# Sch.net
KiCad netlist of a schematic drawn in Altium Designer
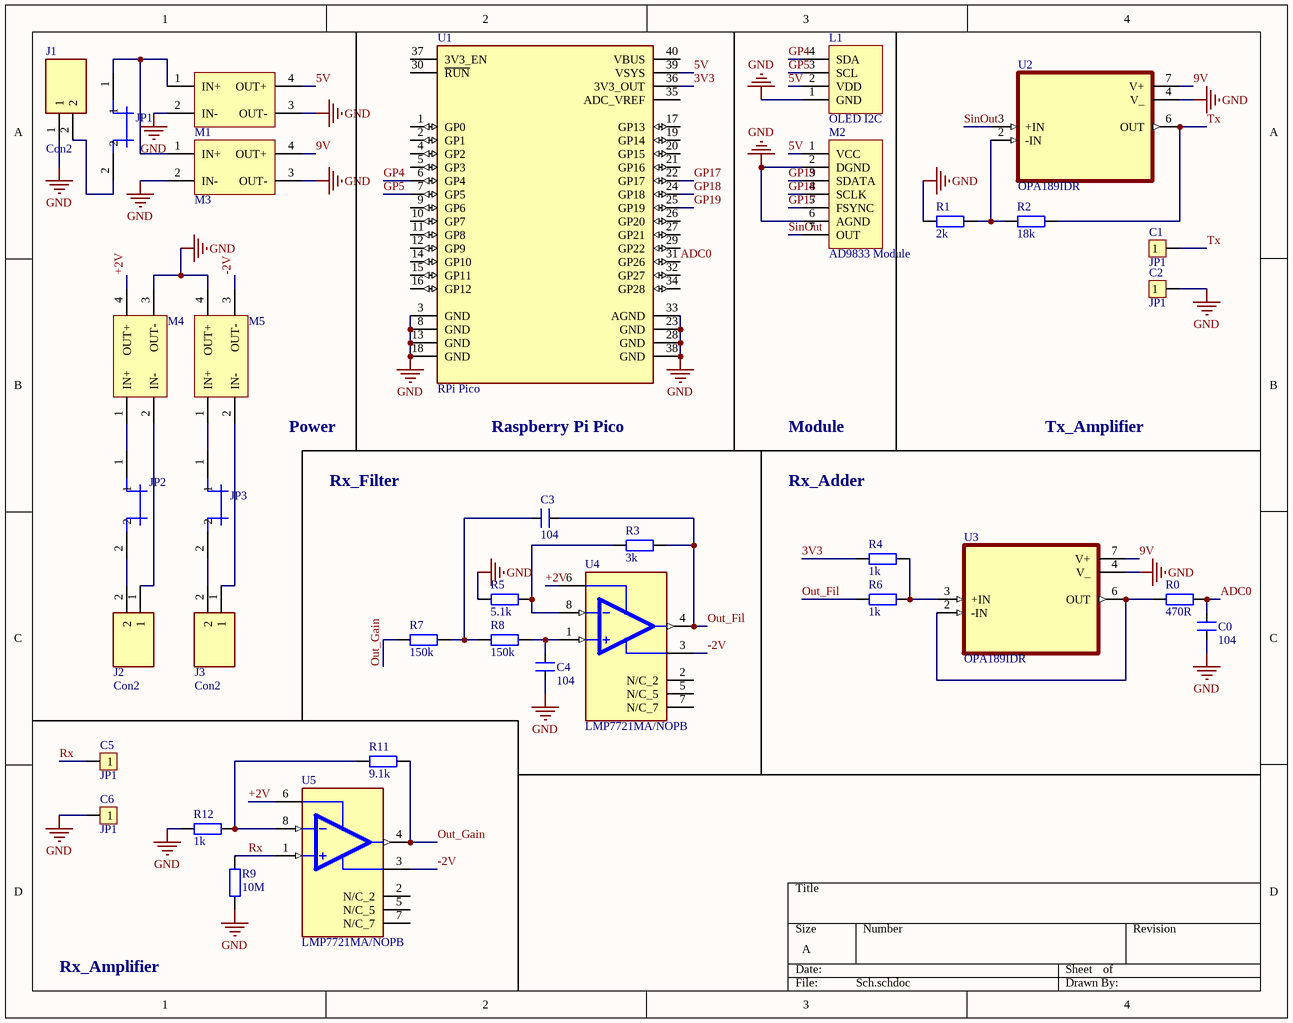
[diagram p0: Sch.schdoc]

(export (version "E")
  (design (tool "Eeschema 10.0.6"))
  (components
    (comp (ref "C0")
      (value "104")
      (footprint "CN2")
      (description "Cap np 104 => 105pF")
      (libsource (lib "Linhkien69") (part "CN2"))
    )
    (comp (ref "C1")
      (value "JP1")
      (footprint "JP1-D1T")
      (description "WR-PHD 2.54 mm Angled Socket Header")
      (fields
        (field (name "MANUFACTURER") "Würth Elektronik eiSos GmbH")
        (field (name "PARTNO") "613002143121")
        (field (name "CREATED BY") "Karrer Zheng")
      )
      (libsource (lib "") (part "JP1_1"))
    )
    (comp (ref "C2")
      (value "JP1")
      (footprint "JP1-D1T")
      (description "WR-PHD 2.54 mm Angled Socket Header")
      (fields
        (field (name "MANUFACTURER") "Würth Elektronik eiSos GmbH")
        (field (name "PARTNO") "613002143121")
        (field (name "CREATED BY") "Karrer Zheng")
      )
      (libsource (lib "") (part "JP1_1"))
    )
    (comp (ref "C3")
      (value "104")
      (footprint "CN2")
      (description "Cap np 104 => 105pF")
      (libsource (lib "Linhkien69") (part "CN2"))
    )
    (comp (ref "C4")
      (value "104")
      (footprint "CN2")
      (description "Cap np 104 => 105pF")
      (libsource (lib "Linhkien69") (part "CN2"))
    )
    (comp (ref "C5")
      (value "JP1")
      (footprint "JP1-D1T")
      (description "WR-PHD 2.54 mm Angled Socket Header")
      (fields
        (field (name "MANUFACTURER") "Würth Elektronik eiSos GmbH")
        (field (name "PARTNO") "613002143121")
        (field (name "CREATED BY") "Karrer Zheng")
      )
      (libsource (lib "Thư Viện Altium FULL HD") (part "JP1"))
    )
    (comp (ref "C6")
      (value "JP1")
      (footprint "JP1-D1T")
      (description "WR-PHD 2.54 mm Angled Socket Header")
      (fields
        (field (name "MANUFACTURER") "Würth Elektronik eiSos GmbH")
        (field (name "PARTNO") "613002143121")
        (field (name "CREATED BY") "Karrer Zheng")
      )
      (libsource (lib "Thư Viện Altium FULL HD") (part "JP1"))
    )
    (comp (ref "J1")
      (value "Con2")
      (footprint "Con_2")
      (fields (field (name "MP") "4-1123723-2"))
      (libsource (lib "") (part "Con2_1"))
    )
    (comp (ref "J2")
      (value "Con2")
      (footprint "Con_2")
      (fields (field (name "MP") "4-1123723-2"))
      (libsource (lib "Duy") (part "Con2"))
    )
    (comp (ref "J3")
      (value "Con2")
      (footprint "Con_2")
      (fields (field (name "MP") "4-1123723-2"))
      (libsource (lib "Duy") (part "Con2"))
    )
    (comp (ref "JP1")
      (value "Jump Con")
      (footprint "Jump_con")
      (description "Low Profile Jumper , Single Row, 2 Positions, 2.54mm (0.100in) Pitch")
      (fields (field (name "MF") "FCI") (field (name "MP") "68786-202LF"))
      (libsource (lib "Duy") (part "Jump Con"))
    )
    (comp (ref "JP2")
      (value "Jump Con")
      (footprint "Jump_con")
      (description "Low Profile Jumper , Single Row, 2 Positions, 2.54mm (0.100in) Pitch")
      (fields (field (name "MF") "FCI") (field (name "MP") "68786-202LF"))
      (libsource (lib "Duy") (part "Jump Con"))
    )
    (comp (ref "JP3")
      (value "Jump Con")
      (footprint "Jump_con")
      (description "Low Profile Jumper , Single Row, 2 Positions, 2.54mm (0.100in) Pitch")
      (fields (field (name "MF") "FCI") (field (name "MP") "68786-202LF"))
      (libsource (lib "Duy") (part "Jump Con"))
    )
    (comp (ref "L1") (value "OLED I2C") (footprint "OLED_I2C") (libsource (lib "Duy") (part "OLED I2C")))
    (comp (ref "M1")
      (value "XL6009 Module")
      (footprint "XL6009_Module")
      (libsource (lib "Duy") (part "XL6009 Module"))
    )
    (comp (ref "M2")
      (value "AD9833 Module")
      (footprint "AD9833_Module")
      (libsource (lib "Duy") (part "AD9833 Module"))
    )
    (comp (ref "M3")
      (value "XL6009 Module")
      (footprint "XL6009_Module")
      (libsource (lib "Duy") (part "XL6009 Module"))
    )
    (comp (ref "M4")
      (value "LM2596S Module")
      (footprint "LM2596S_Module")
      (libsource (lib "Duy") (part "LM2596S Module"))
    )
    (comp (ref "M5")
      (value "LM2596S Module")
      (footprint "LM2596S_Module")
      (libsource (lib "Duy") (part "LM2596S Module"))
    )
    (comp (ref "R0")
      (value "470R")
      (footprint "R1/4W")
      (description "Resistor 1/4W")
      (libsource (lib "syhaunguyen") (part "R1/4W"))
    )
    (comp (ref "R1")
      (value "2k")
      (footprint "R1/4W")
      (description "Resistor 1/4W")
      (libsource (lib "syhaunguyen") (part "R1/4W"))
    )
    (comp (ref "R2")
      (value "18k")
      (footprint "R1/4W")
      (description "Resistor 1/4W")
      (libsource (lib "syhaunguyen") (part "R1/4W"))
    )
    (comp (ref "R3")
      (value "3k")
      (footprint "R1/4W")
      (description "Resistor 1/4W")
      (libsource (lib "syhaunguyen") (part "R1/4W"))
    )
    (comp (ref "R4")
      (value "1k")
      (footprint "R1/4W")
      (description "Resistor 1/4W")
      (libsource (lib "syhaunguyen") (part "R1/4W"))
    )
    (comp (ref "R5")
      (value "5.1k")
      (footprint "R1/4W")
      (description "Resistor 1/4W")
      (libsource (lib "syhaunguyen") (part "R1/4W"))
    )
    (comp (ref "R6")
      (value "1k")
      (footprint "R1/4W")
      (description "Resistor 1/4W")
      (libsource (lib "syhaunguyen") (part "R1/4W"))
    )
    (comp (ref "R7")
      (value "150k")
      (footprint "R1/4W")
      (description "Resistor 1/4W")
      (libsource (lib "syhaunguyen") (part "R1/4W"))
    )
    (comp (ref "R8")
      (value "150k")
      (footprint "R1/4W")
      (description "Resistor 1/4W")
      (libsource (lib "syhaunguyen") (part "R1/4W"))
    )
    (comp (ref "R9")
      (value "10M")
      (footprint "R1/4W")
      (description "Resistor 1/4W")
      (libsource (lib "syhaunguyen") (part "R1/4W"))
    )
    (comp (ref "R11")
      (value "9.1k")
      (footprint "R1/4W")
      (description "Resistor 1/4W")
      (libsource (lib "syhaunguyen") (part "R1/4W"))
    )
    (comp (ref "R12")
      (value "1k")
      (footprint "R1/4W")
      (description "Resistor 1/4W")
      (libsource (lib "syhaunguyen") (part "R1/4W"))
    )
    (comp (ref "U1")
      (value "RPi Pico")
      (footprint "RPI_PICO")
      (description "RP2040 Raspberry Pi Pico - ARM Cortex-M0+ MCU 32-Bit Embedded Evaluation Board")
      (fields (field (name "MP") "SC0915"))
      (libsource (lib "Duy") (part "RPi Pico"))
    )
    (comp (ref "U2")
      (value "OPA189IDR")
      (footprint "SOIC127P599X175-8N")
      (fields (field (name "DIGI-KEY_PART_NUMBER") "296-48941-1-ND") (field (name "MF") "Texas Instruments"))
      (libsource (lib "Duy") (part "OPA189IDR"))
    )
    (comp (ref "U3")
      (value "OPA189IDR")
      (footprint "SOIC127P599X175-8N")
      (fields (field (name "DIGI-KEY_PART_NUMBER") "296-48941-1-ND") (field (name "MF") "Texas Instruments"))
      (libsource (lib "Duy") (part "OPA189IDR"))
    )
    (comp (ref "U4")
      (value "LMP7721MA/NOPB")
      (footprint "SOIC127P599X175-8N - duplicate")
      (description "3 Femtoampere Input Bias Current Precision Amplifier 8-SOIC -40 to 125")
      (fields (field (name "MF") "Texas Instruments"))
      (libsource (lib "Duy") (part "LMP7721MA/NOPB"))
    )
    (comp (ref "U5")
      (value "LMP7721MA/NOPB")
      (footprint "SOIC127P599X175-8N - duplicate")
      (description "3 Femtoampere Input Bias Current Precision Amplifier 8-SOIC -40 to 125")
      (fields (field (name "MF") "Texas Instruments"))
      (libsource (lib "Duy") (part "LMP7721MA/NOPB"))
    )
  )
  (nets
    (net (code "1") (name "/+2V") (class "Default")
      (node (ref "M4") (pin "4") (pinfunction "OUT+_4") (pintype "passive"))
      (node (ref "U4") (pin "6") (pinfunction "V+_6") (pintype "power_in"))
      (node (ref "U5") (pin "6") (pinfunction "V+_6") (pintype "power_in"))
    )
    (net (code "2") (name "/-2V") (class "Default")
      (node (ref "M5") (pin "3") (pinfunction "OUT-_3") (pintype "passive"))
      (node (ref "U4") (pin "3") (pinfunction "V-_3") (pintype "power_in"))
      (node (ref "U5") (pin "3") (pinfunction "V-_3") (pintype "power_in"))
    )
    (net (code "3") (name "/3V3") (class "Default")
      (node (ref "R4") (pin "1") (pinfunction "1_1") (pintype "passive"))
      (node (ref "U1") (pin "36") (pinfunction "3V3_OUT_36") (pintype "power_in"))
    )
    (net (code "4") (name "/5V") (class "Default")
      (node (ref "L1") (pin "2") (pinfunction "VDD_2") (pintype "passive"))
      (node (ref "M1") (pin "4") (pinfunction "OUT+_4") (pintype "passive"))
      (node (ref "M2") (pin "1") (pinfunction "VCC_1") (pintype "passive"))
      (node (ref "U1") (pin "39") (pinfunction "VSYS_39") (pintype "power_in"))
    )
    (net (code "5") (name "/9V") (class "Default")
      (node (ref "M3") (pin "4") (pinfunction "OUT+_4") (pintype "passive"))
      (node (ref "U2") (pin "7") (pinfunction "V+_7") (pintype "power_in"))
      (node (ref "U3") (pin "7") (pinfunction "V+_7") (pintype "power_in"))
    )
    (net (code "6") (name "/ADC0") (class "Default")
      (node (ref "C0") (pin "2") (pinfunction "2_2") (pintype "passive"))
      (node (ref "R0") (pin "2") (pinfunction "2_2") (pintype "passive"))
      (node (ref "U1") (pin "31") (pinfunction "GP26_31") (pintype "bidirectional"))
    )
    (net (code "7") (name "/GP4") (class "Default")
      (node (ref "L1") (pin "4") (pinfunction "SDA_4") (pintype "passive"))
      (node (ref "U1") (pin "6") (pinfunction "GP4_6") (pintype "bidirectional"))
    )
    (net (code "8") (name "/GP5") (class "Default")
      (node (ref "L1") (pin "3") (pinfunction "SCL_3") (pintype "passive"))
      (node (ref "U1") (pin "7") (pinfunction "GP5_7") (pintype "bidirectional"))
    )
    (net (code "9") (name "/GP17") (class "Default")
      (node (ref "M2") (pin "5") (pinfunction "FSYNC_5") (pintype "passive"))
      (node (ref "U1") (pin "22") (pinfunction "GP17_22") (pintype "bidirectional"))
    )
    (net (code "10") (name "/GP18") (class "Default")
      (node (ref "M2") (pin "4") (pinfunction "SCLK_4") (pintype "passive"))
      (node (ref "U1") (pin "24") (pinfunction "GP18_24") (pintype "bidirectional"))
    )
    (net (code "11") (name "/GP19") (class "Default")
      (node (ref "M2") (pin "3") (pinfunction "SDATA_3") (pintype "passive"))
      (node (ref "U1") (pin "25") (pinfunction "GP19_25") (pintype "bidirectional"))
    )
    (net (code "12") (name "/Out_Fil") (class "Default")
      (node (ref "C3") (pin "2") (pinfunction "2_2") (pintype "passive"))
      (node (ref "R3") (pin "2") (pinfunction "2_2") (pintype "passive"))
      (node (ref "R6") (pin "1") (pinfunction "1_1") (pintype "passive"))
      (node (ref "U4") (pin "4") (pinfunction "VOUT_4") (pintype "output"))
    )
    (net (code "13") (name "/Out_Gain") (class "Default")
      (node (ref "R11") (pin "2") (pinfunction "2_2") (pintype "passive"))
      (node (ref "R7") (pin "1") (pinfunction "1_1") (pintype "passive"))
      (node (ref "U5") (pin "4") (pinfunction "VOUT_4") (pintype "output"))
    )
    (net (code "14") (name "/Rx") (class "Default")
      (node (ref "C5") (pin "1") (pinfunction "1_1") (pintype "passive"))
      (node (ref "R9") (pin "1") (pinfunction "1_1") (pintype "passive"))
      (node (ref "U5") (pin "1") (pinfunction "IN+_1") (pintype "input"))
    )
    (net (code "15") (name "/SinOut") (class "Default")
      (node (ref "M2") (pin "7") (pinfunction "OUT_7") (pintype "passive"))
      (node (ref "U2") (pin "3") (pinfunction "+IN_3") (pintype "input"))
    )
    (net (code "16") (name "/Tx") (class "Default")
      (node (ref "C1") (pin "1") (pinfunction "1_1") (pintype "passive"))
      (node (ref "R2") (pin "2") (pinfunction "2_2") (pintype "passive"))
      (node (ref "U2") (pin "6") (pinfunction "OUT_6") (pintype "output"))
    )
    (net (code "17") (name "GND") (class "Default")
      (node (ref "C0") (pin "1") (pinfunction "1_1") (pintype "passive"))
      (node (ref "C2") (pin "1") (pinfunction "1_1") (pintype "passive"))
      (node (ref "C4") (pin "1") (pinfunction "1_1") (pintype "passive"))
      (node (ref "C6") (pin "1") (pinfunction "1_1") (pintype "passive"))
      (node (ref "J1") (pin "1") (pinfunction "1_1") (pintype "passive"))
      (node (ref "L1") (pin "1") (pinfunction "GND_1") (pintype "passive"))
      (node (ref "M1") (pin "2") (pinfunction "IN-_2") (pintype "passive"))
      (node (ref "M1") (pin "3") (pinfunction "OUT-_3") (pintype "passive"))
      (node (ref "M2") (pin "2") (pinfunction "DGND_2") (pintype "passive"))
      (node (ref "M2") (pin "6") (pinfunction "AGND_6") (pintype "passive"))
      (node (ref "M3") (pin "2") (pinfunction "IN-_2") (pintype "passive"))
      (node (ref "M3") (pin "3") (pinfunction "OUT-_3") (pintype "passive"))
      (node (ref "M4") (pin "3") (pinfunction "OUT-_3") (pintype "passive"))
      (node (ref "M5") (pin "4") (pinfunction "OUT+_4") (pintype "passive"))
      (node (ref "R1") (pin "1") (pinfunction "1_1") (pintype "passive"))
      (node (ref "R12") (pin "2") (pinfunction "2_2") (pintype "passive"))
      (node (ref "R5") (pin "1") (pinfunction "1_1") (pintype "passive"))
      (node (ref "R9") (pin "2") (pinfunction "2_2") (pintype "passive"))
      (node (ref "U1") (pin "13") (pinfunction "GND_13") (pintype "power_in"))
      (node (ref "U1") (pin "18") (pinfunction "GND_18") (pintype "power_in"))
      (node (ref "U1") (pin "23") (pinfunction "GND_23") (pintype "power_in"))
      (node (ref "U1") (pin "28") (pinfunction "GND_28") (pintype "power_in"))
      (node (ref "U1") (pin "3") (pinfunction "GND_3") (pintype "power_in"))
      (node (ref "U1") (pin "33") (pinfunction "AGND_33") (pintype "power_in"))
      (node (ref "U1") (pin "38") (pinfunction "GND_38") (pintype "power_in"))
      (node (ref "U1") (pin "8") (pinfunction "GND_8") (pintype "power_in"))
      (node (ref "U2") (pin "4") (pinfunction "V__4") (pintype "power_in"))
      (node (ref "U3") (pin "4") (pinfunction "V__4") (pintype "power_in"))
    )
    (net (code "18") (name "Net-(C3-Pad1)") (class "Default")
      (node (ref "C3") (pin "1") (pinfunction "1_1") (pintype "passive"))
      (node (ref "R7") (pin "2") (pinfunction "2_2") (pintype "passive"))
      (node (ref "R8") (pin "1") (pinfunction "1_1") (pintype "passive"))
    )
    (net (code "19") (name "Net-(J1-Pad2)") (class "Default")
      (node (ref "J1") (pin "2") (pinfunction "2_2") (pintype "passive"))
      (node (ref "JP1") (pin "2") (pinfunction "2_2") (pintype "passive"))
    )
    (net (code "20") (name "Net-(J2-Pad2)") (class "Default")
      (node (ref "J2") (pin "2") (pinfunction "2_2") (pintype "passive"))
      (node (ref "JP2") (pin "2") (pinfunction "2_2") (pintype "passive"))
    )
    (net (code "21") (name "Net-(J3-Pad2)") (class "Default")
      (node (ref "J3") (pin "2") (pinfunction "2_2") (pintype "passive"))
      (node (ref "JP3") (pin "2") (pinfunction "2_2") (pintype "passive"))
    )
    (net (code "22") (name "Net-(M1-IN+)") (class "Default")
      (node (ref "JP1") (pin "1") (pinfunction "1_1") (pintype "passive"))
      (node (ref "M1") (pin "1") (pinfunction "IN+_1") (pintype "passive"))
      (node (ref "M3") (pin "1") (pinfunction "IN+_1") (pintype "passive"))
    )
    (net (code "23") (name "Net-(M4-IN+)") (class "Default")
      (node (ref "JP2") (pin "1") (pinfunction "1_1") (pintype "passive"))
      (node (ref "M4") (pin "1") (pinfunction "IN+_1") (pintype "passive"))
    )
    (net (code "24") (name "Net-(M4-IN-)") (class "Default")
      (node (ref "J2") (pin "1") (pinfunction "1_1") (pintype "passive"))
      (node (ref "M4") (pin "2") (pinfunction "IN-_2") (pintype "passive"))
    )
    (net (code "25") (name "Net-(M5-IN+)") (class "Default")
      (node (ref "JP3") (pin "1") (pinfunction "1_1") (pintype "passive"))
      (node (ref "M5") (pin "1") (pinfunction "IN+_1") (pintype "passive"))
    )
    (net (code "26") (name "Net-(M5-IN-)") (class "Default")
      (node (ref "J3") (pin "1") (pinfunction "1_1") (pintype "passive"))
      (node (ref "M5") (pin "2") (pinfunction "IN-_2") (pintype "passive"))
    )
    (net (code "27") (name "Net-(U2--IN)") (class "Default")
      (node (ref "R1") (pin "2") (pinfunction "2_2") (pintype "passive"))
      (node (ref "R2") (pin "1") (pinfunction "1_1") (pintype "passive"))
      (node (ref "U2") (pin "2") (pinfunction "-IN_2") (pintype "input"))
    )
    (net (code "28") (name "Net-(U3-+IN)") (class "Default")
      (node (ref "R4") (pin "2") (pinfunction "2_2") (pintype "passive"))
      (node (ref "R6") (pin "2") (pinfunction "2_2") (pintype "passive"))
      (node (ref "U3") (pin "3") (pinfunction "+IN_3") (pintype "input"))
    )
    (net (code "29") (name "Net-(U3--IN)") (class "Default")
      (node (ref "R0") (pin "1") (pinfunction "1_1") (pintype "passive"))
      (node (ref "U3") (pin "2") (pinfunction "-IN_2") (pintype "input"))
      (node (ref "U3") (pin "6") (pinfunction "OUT_6") (pintype "output"))
    )
    (net (code "30") (name "Net-(U4-IN+)") (class "Default")
      (node (ref "C4") (pin "2") (pinfunction "2_2") (pintype "passive"))
      (node (ref "R8") (pin "2") (pinfunction "2_2") (pintype "passive"))
      (node (ref "U4") (pin "1") (pinfunction "IN+_1") (pintype "input"))
    )
    (net (code "31") (name "Net-(U4-IN-)") (class "Default")
      (node (ref "R3") (pin "1") (pinfunction "1_1") (pintype "passive"))
      (node (ref "R5") (pin "2") (pinfunction "2_2") (pintype "passive"))
      (node (ref "U4") (pin "8") (pinfunction "IN-_8") (pintype "input"))
    )
    (net (code "32") (name "Net-(U5-IN-)") (class "Default")
      (node (ref "R11") (pin "1") (pinfunction "1_1") (pintype "passive"))
      (node (ref "R12") (pin "1") (pinfunction "1_1") (pintype "passive"))
      (node (ref "U5") (pin "8") (pinfunction "IN-_8") (pintype "input"))
    )
    (net (code "33") (name "unconnected-(U1-3V3_EN-Pad37)") (class "Default")
      (node (ref "U1") (pin "37") (pinfunction "3V3_EN_37") (pintype "power_in"))
    )
    (net (code "34") (name "unconnected-(U1-ADC_VREF-Pad35)") (class "Default")
      (node (ref "U1") (pin "35") (pinfunction "ADC_VREF_35") (pintype "power_in"))
    )
    (net (code "35") (name "unconnected-(U1-GP0-Pad1)") (class "Default")
      (node (ref "U1") (pin "1") (pinfunction "GP0_1") (pintype "bidirectional"))
    )
    (net (code "36") (name "unconnected-(U1-GP1-Pad2)") (class "Default")
      (node (ref "U1") (pin "2") (pinfunction "GP1_2") (pintype "bidirectional"))
    )
    (net (code "37") (name "unconnected-(U1-GP2-Pad4)") (class "Default")
      (node (ref "U1") (pin "4") (pinfunction "GP2_4") (pintype "bidirectional"))
    )
    (net (code "38") (name "unconnected-(U1-GP3-Pad5)") (class "Default")
      (node (ref "U1") (pin "5") (pinfunction "GP3_5") (pintype "bidirectional"))
    )
    (net (code "39") (name "unconnected-(U1-GP6-Pad9)") (class "Default")
      (node (ref "U1") (pin "9") (pinfunction "GP6_9") (pintype "bidirectional"))
    )
    (net (code "40") (name "unconnected-(U1-GP7-Pad10)") (class "Default")
      (node (ref "U1") (pin "10") (pinfunction "GP7_10") (pintype "bidirectional"))
    )
    (net (code "41") (name "unconnected-(U1-GP8-Pad11)") (class "Default")
      (node (ref "U1") (pin "11") (pinfunction "GP8_11") (pintype "bidirectional"))
    )
    (net (code "42") (name "unconnected-(U1-GP9-Pad12)") (class "Default")
      (node (ref "U1") (pin "12") (pinfunction "GP9_12") (pintype "bidirectional"))
    )
    (net (code "43") (name "unconnected-(U1-GP10-Pad14)") (class "Default")
      (node (ref "U1") (pin "14") (pinfunction "GP10_14") (pintype "bidirectional"))
    )
    (net (code "44") (name "unconnected-(U1-GP11-Pad15)") (class "Default")
      (node (ref "U1") (pin "15") (pinfunction "GP11_15") (pintype "bidirectional"))
    )
    (net (code "45") (name "unconnected-(U1-GP12-Pad16)") (class "Default")
      (node (ref "U1") (pin "16") (pinfunction "GP12_16") (pintype "bidirectional"))
    )
    (net (code "46") (name "unconnected-(U1-GP13-Pad17)") (class "Default")
      (node (ref "U1") (pin "17") (pinfunction "GP13_17") (pintype "bidirectional"))
    )
    (net (code "47") (name "unconnected-(U1-GP14-Pad19)") (class "Default")
      (node (ref "U1") (pin "19") (pinfunction "GP14_19") (pintype "bidirectional"))
    )
    (net (code "48") (name "unconnected-(U1-GP15-Pad20)") (class "Default")
      (node (ref "U1") (pin "20") (pinfunction "GP15_20") (pintype "bidirectional"))
    )
    (net (code "49") (name "unconnected-(U1-GP16-Pad21)") (class "Default")
      (node (ref "U1") (pin "21") (pinfunction "GP16_21") (pintype "bidirectional"))
    )
    (net (code "50") (name "unconnected-(U1-GP20-Pad26)") (class "Default")
      (node (ref "U1") (pin "26") (pinfunction "GP20_26") (pintype "bidirectional"))
    )
    (net (code "51") (name "unconnected-(U1-GP21-Pad27)") (class "Default")
      (node (ref "U1") (pin "27") (pinfunction "GP21_27") (pintype "bidirectional"))
    )
    (net (code "52") (name "unconnected-(U1-GP22-Pad29)") (class "Default")
      (node (ref "U1") (pin "29") (pinfunction "GP22_29") (pintype "bidirectional"))
    )
    (net (code "53") (name "unconnected-(U1-GP27-Pad32)") (class "Default")
      (node (ref "U1") (pin "32") (pinfunction "GP27_32") (pintype "bidirectional"))
    )
    (net (code "54") (name "unconnected-(U1-GP28-Pad34)") (class "Default")
      (node (ref "U1") (pin "34") (pinfunction "GP28_34") (pintype "bidirectional"))
    )
    (net (code "55") (name "unconnected-(U1-VBUS-Pad40)") (class "Default")
      (node (ref "U1") (pin "40") (pinfunction "VBUS_40") (pintype "power_in"))
    )
    (net (code "56") (name "unconnected-(U1-~{RUN}-Pad30)") (class "Default")
      (node (ref "U1") (pin "30") (pinfunction "~{RUN}_30") (pintype "power_in"))
    )
    (net (code "57") (name "unconnected-(U4-N{slash}C_2-Pad2)") (class "Default")
      (node (ref "U4") (pin "2") (pinfunction "N/C_2_2") (pintype "passive"))
    )
    (net (code "58") (name "unconnected-(U4-N{slash}C_5-Pad5)") (class "Default")
      (node (ref "U4") (pin "5") (pinfunction "N/C_5_5") (pintype "passive"))
    )
    (net (code "59") (name "unconnected-(U4-N{slash}C_7-Pad7)") (class "Default")
      (node (ref "U4") (pin "7") (pinfunction "N/C_7_7") (pintype "passive"))
    )
    (net (code "60") (name "unconnected-(U5-N{slash}C_2-Pad2)") (class "Default")
      (node (ref "U5") (pin "2") (pinfunction "N/C_2_2") (pintype "passive"))
    )
    (net (code "61") (name "unconnected-(U5-N{slash}C_5-Pad5)") (class "Default")
      (node (ref "U5") (pin "5") (pinfunction "N/C_5_5") (pintype "passive"))
    )
    (net (code "62") (name "unconnected-(U5-N{slash}C_7-Pad7)") (class "Default")
      (node (ref "U5") (pin "7") (pinfunction "N/C_7_7") (pintype "passive"))
    )
  )
)
